# Voltage_Controlled_Amplifier_v1.net
KiCad netlist of a schematic drawn in EAGLE
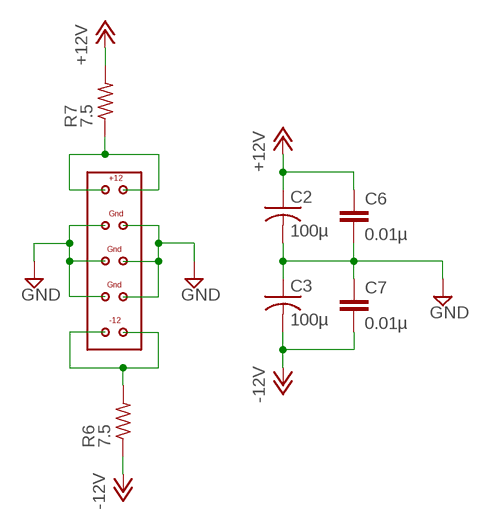
[diagram p0: schematic, sheet 1]
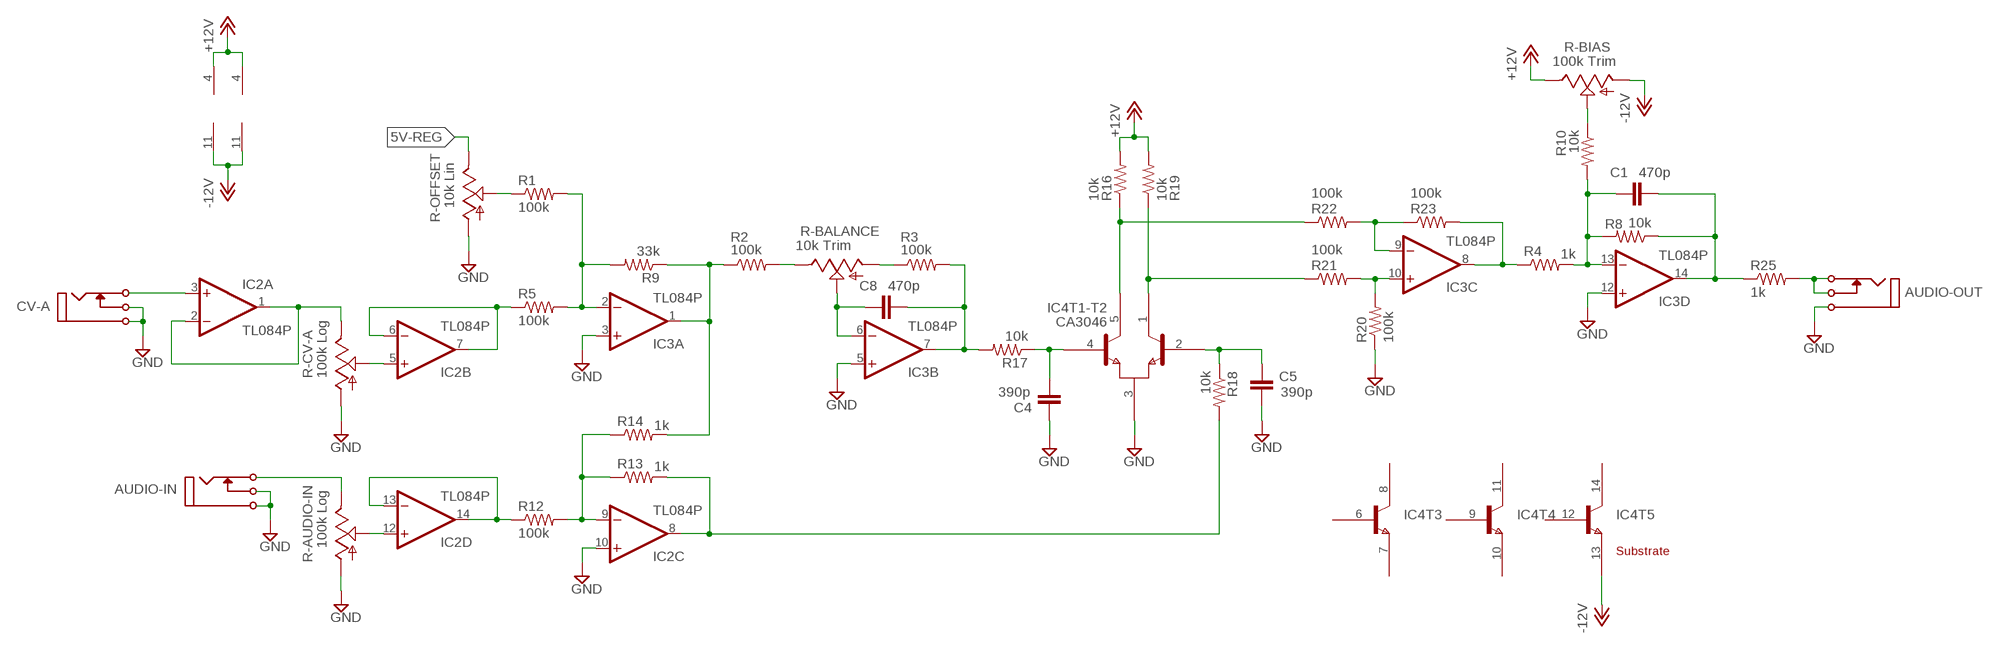
[diagram p1: schematic, sheet 2]

(export (version "E")
  (design (tool "Eeschema 10.0.6"))
  (components
    (comp (ref "C2")
      (value "100µ")
      (footprint "eagle-import:C025-050X050")
      (libsource (lib "eagle-import") (part "C-US025-050X050"))
    )
    (comp (ref "C3")
      (value "100µ")
      (footprint "eagle-import:C025-050X050")
      (libsource (lib "eagle-import") (part "C-US025-050X050"))
    )
    (comp (ref "C6")
      (value "0.01µ")
      (footprint "eagle-import:C2.5-2")
      (libsource (lib "eagle-import") (part "C2.5/2"))
    )
    (comp (ref "C7")
      (value "0.01µ")
      (footprint "eagle-import:C2.5-2")
      (libsource (lib "eagle-import") (part "C2.5/2"))
    )
    (comp (ref "R6")
      (value "7.5")
      (footprint "eagle-import:0204_7")
      (libsource (lib "eagle-import") (part "R-US_0204/7"))
    )
    (comp (ref "R7")
      (value "7.5")
      (footprint "eagle-import:0204_7")
      (libsource (lib "eagle-import") (part "R-US_0204/7"))
    )
    (comp (ref "U$1")
      (value "EURORACK-POWER")
      (footprint "eagle-import:EURORACK-POWER")
      (libsource (lib "eagle-import") (part "EURORACK-POWER"))
    )
    (comp (ref "AUDIO-IN")
      (value "I/O")
      (footprint "eagle-import:MONO_JACK")
      (libsource (lib "eagle-import") (part "MONO_JACK"))
    )
    (comp (ref "AUDIO-OUT")
      (value "I/O")
      (footprint "eagle-import:MONO_JACK")
      (libsource (lib "eagle-import") (part "MONO_JACK"))
    )
    (comp (ref "C1")
      (value "470p")
      (footprint "eagle-import:C2.5-2")
      (libsource (lib "eagle-import") (part "C2.5/2"))
    )
    (comp (ref "C4")
      (value "390p")
      (footprint "eagle-import:C2.5-2")
      (libsource (lib "eagle-import") (part "C2.5/2"))
    )
    (comp (ref "C5")
      (value "390p")
      (footprint "eagle-import:C2.5-2")
      (libsource (lib "eagle-import") (part "C2.5/2"))
    )
    (comp (ref "C8")
      (value "470p")
      (footprint "eagle-import:C2.5-2")
      (libsource (lib "eagle-import") (part "C2.5/2"))
    )
    (comp (ref "CV-A")
      (value "I/O")
      (footprint "eagle-import:MONO_JACK")
      (libsource (lib "eagle-import") (part "MONO_JACK"))
    )
    (comp (ref "IC2")
      (value "TL084P")
      (footprint "eagle-import:DIL14")
      (libsource (lib "eagle-import") (part "TL084P"))
    )
    (comp (ref "IC3")
      (value "TL084P")
      (footprint "eagle-import:DIL14")
      (libsource (lib "eagle-import") (part "TL084P"))
    )
    (comp (ref "IC4")
      (value "CA3046")
      (footprint "eagle-import:DIL14")
      (libsource (lib "eagle-import") (part "CA3046"))
    )
    (comp (ref "R-AUDIO-IN")
      (value "100k Log")
      (footprint "eagle-import:B64Y")
      (libsource (lib "eagle-import") (part "TRIM_US-B64Y"))
    )
    (comp (ref "R-BALANCE")
      (value "10k Trim")
      (footprint "eagle-import:B64Y")
      (libsource (lib "eagle-import") (part "TRIM_US-B64Y"))
    )
    (comp (ref "R-BIAS")
      (value "100k Trim")
      (footprint "eagle-import:B64Y")
      (libsource (lib "eagle-import") (part "TRIM_US-B64Y"))
    )
    (comp (ref "R-CV-A")
      (value "100k Log")
      (footprint "eagle-import:B64Y")
      (libsource (lib "eagle-import") (part "TRIM_US-B64Y"))
    )
    (comp (ref "R-OFFSET")
      (value "10k Lin")
      (footprint "eagle-import:B64Y")
      (libsource (lib "eagle-import") (part "TRIM_US-B64Y"))
    )
    (comp (ref "R1")
      (value "100k")
      (footprint "eagle-import:0204V")
      (libsource (lib "eagle-import") (part "R-US_0204/2V"))
    )
    (comp (ref "R2")
      (value "100k")
      (footprint "eagle-import:0204V")
      (libsource (lib "eagle-import") (part "R-US_0204/2V"))
    )
    (comp (ref "R3")
      (value "100k")
      (footprint "eagle-import:0204V")
      (libsource (lib "eagle-import") (part "R-US_0204/2V"))
    )
    (comp (ref "R4")
      (value "1k")
      (footprint "eagle-import:0204V")
      (libsource (lib "eagle-import") (part "R-US_0204/2V"))
    )
    (comp (ref "R5")
      (value "100k")
      (footprint "eagle-import:0204V")
      (libsource (lib "eagle-import") (part "R-US_0204/2V"))
    )
    (comp (ref "R8")
      (value "10k")
      (footprint "eagle-import:0204V")
      (libsource (lib "eagle-import") (part "R-US_0204/2V"))
    )
    (comp (ref "R9")
      (value "33k")
      (footprint "eagle-import:0204V")
      (libsource (lib "eagle-import") (part "R-US_0204/2V"))
    )
    (comp (ref "R10")
      (value "10k")
      (footprint "eagle-import:0204V")
      (libsource (lib "eagle-import") (part "R-US_0204/2V"))
    )
    (comp (ref "R12")
      (value "100k")
      (footprint "eagle-import:0204V")
      (libsource (lib "eagle-import") (part "R-US_0204/2V"))
    )
    (comp (ref "R13")
      (value "1k")
      (footprint "eagle-import:0204V")
      (libsource (lib "eagle-import") (part "R-US_0204/2V"))
    )
    (comp (ref "R14")
      (value "1k")
      (footprint "eagle-import:0204V")
      (libsource (lib "eagle-import") (part "R-US_0204/2V"))
    )
    (comp (ref "R16")
      (value "10k")
      (footprint "eagle-import:0204V")
      (libsource (lib "eagle-import") (part "R-US_0204/2V"))
    )
    (comp (ref "R17")
      (value "10k")
      (footprint "eagle-import:0204V")
      (libsource (lib "eagle-import") (part "R-US_0204/2V"))
    )
    (comp (ref "R18")
      (value "10k")
      (footprint "eagle-import:0204_7")
      (libsource (lib "eagle-import") (part "R-US_0204/7"))
    )
    (comp (ref "R19")
      (value "10k")
      (footprint "eagle-import:0204V")
      (libsource (lib "eagle-import") (part "R-US_0204/2V"))
    )
    (comp (ref "R20")
      (value "100k")
      (footprint "eagle-import:0204V")
      (libsource (lib "eagle-import") (part "R-US_0204/2V"))
    )
    (comp (ref "R21")
      (value "100k")
      (footprint "eagle-import:0204V")
      (libsource (lib "eagle-import") (part "R-US_0204/2V"))
    )
    (comp (ref "R22")
      (value "100k")
      (footprint "eagle-import:0204V")
      (libsource (lib "eagle-import") (part "R-US_0204/2V"))
    )
    (comp (ref "R23")
      (value "100k")
      (footprint "eagle-import:0204V")
      (libsource (lib "eagle-import") (part "R-US_0204/2V"))
    )
    (comp (ref "R25")
      (value "1k")
      (footprint "eagle-import:0204_7")
      (libsource (lib "eagle-import") (part "R-US_0204/7"))
    )
  )
  (nets
    (net (code "1") (name "+12V") (class "Default")
      (node (ref "C2") (pin "1") (pinfunction "1_1") (pintype "passive"))
      (node (ref "C6") (pin "1") (pinfunction "1_1") (pintype "passive"))
      (node (ref "IC2") (pin "4") (pinfunction "V+_4") (pintype "power_in"))
      (node (ref "IC3") (pin "4") (pinfunction "V+_4") (pintype "power_in"))
      (node (ref "R-BIAS") (pin "E") (pinfunction "E_E") (pintype "passive"))
      (node (ref "R16") (pin "2") (pinfunction "2_2") (pintype "passive"))
      (node (ref "R19") (pin "2") (pinfunction "2_2") (pintype "passive"))
      (node (ref "R7") (pin "2") (pinfunction "2_2") (pintype "passive"))
    )
    (net (code "2") (name "-12V") (class "Default")
      (node (ref "C3") (pin "2") (pinfunction "2_2") (pintype "passive"))
      (node (ref "C7") (pin "2") (pinfunction "2_2") (pintype "passive"))
      (node (ref "IC2") (pin "11") (pinfunction "V-_11") (pintype "power_in"))
      (node (ref "IC3") (pin "11") (pinfunction "V-_11") (pintype "power_in"))
      (node (ref "IC4") (pin "13") (pinfunction "E_13") (pintype "passive"))
      (node (ref "R-BIAS") (pin "A") (pinfunction "A_A") (pintype "passive"))
      (node (ref "R6") (pin "1") (pinfunction "1_1") (pintype "passive"))
    )
    (net (code "3") (name "5V-REG") (class "Default")
      (node (ref "R-OFFSET") (pin "E") (pinfunction "E_E") (pintype "passive"))
    )
    (net (code "4") (name "GND") (class "Default")
      (node (ref "AUDIO-IN") (pin "P$1") (pinfunction "P$1_P$1") (pintype "bidirectional"))
      (node (ref "AUDIO-IN") (pin "P$3") (pinfunction "P3_P$3") (pintype "bidirectional"))
      (node (ref "AUDIO-OUT") (pin "P$1") (pinfunction "P$1_P$1") (pintype "bidirectional"))
      (node (ref "C2") (pin "2") (pinfunction "2_2") (pintype "passive"))
      (node (ref "C3") (pin "1") (pinfunction "1_1") (pintype "passive"))
      (node (ref "C4") (pin "1") (pinfunction "1_1") (pintype "passive"))
      (node (ref "C5") (pin "2") (pinfunction "2_2") (pintype "passive"))
      (node (ref "C6") (pin "2") (pinfunction "2_2") (pintype "passive"))
      (node (ref "C7") (pin "1") (pinfunction "1_1") (pintype "passive"))
      (node (ref "CV-A") (pin "P$1") (pinfunction "P$1_P$1") (pintype "bidirectional"))
      (node (ref "CV-A") (pin "P$3") (pinfunction "P3_P$3") (pintype "bidirectional"))
      (node (ref "IC2") (pin "10") (pinfunction "+IN_10") (pintype "input"))
      (node (ref "IC3") (pin "12") (pinfunction "+IN_12") (pintype "input"))
      (node (ref "IC3") (pin "3") (pinfunction "+IN_3") (pintype "input"))
      (node (ref "IC3") (pin "5") (pinfunction "+IN_5") (pintype "input"))
      (node (ref "IC4") (pin "3") (pinfunction "E_3") (pintype "passive"))
      (node (ref "R-AUDIO-IN") (pin "A") (pinfunction "A_A") (pintype "passive"))
      (node (ref "R-CV-A") (pin "A") (pinfunction "A_A") (pintype "passive"))
      (node (ref "R-OFFSET") (pin "A") (pinfunction "A_A") (pintype "passive"))
      (node (ref "R20") (pin "1") (pinfunction "1_1") (pintype "passive"))
      (node (ref "U$1") (pin "P$3") (pinfunction "P$3_P$3") (pintype "bidirectional"))
      (node (ref "U$1") (pin "P$4") (pinfunction "P$4_P$4") (pintype "bidirectional"))
      (node (ref "U$1") (pin "P$5") (pinfunction "P$5_P$5") (pintype "bidirectional"))
      (node (ref "U$1") (pin "P$6") (pinfunction "P$6_P$6") (pintype "bidirectional"))
      (node (ref "U$1") (pin "P$7") (pinfunction "P$7_P$7") (pintype "bidirectional"))
      (node (ref "U$1") (pin "P$8") (pinfunction "P$8_P$8") (pintype "bidirectional"))
    )
    (net (code "5") (name "Net-(AUDIO-IN-P2)") (class "Default")
      (node (ref "AUDIO-IN") (pin "P$2") (pinfunction "P2_P$2") (pintype "bidirectional"))
      (node (ref "R-AUDIO-IN") (pin "E") (pinfunction "E_E") (pintype "passive"))
    )
    (net (code "6") (name "Net-(AUDIO-OUT-P2)") (class "Default")
      (node (ref "AUDIO-OUT") (pin "P$2") (pinfunction "P2_P$2") (pintype "bidirectional"))
      (node (ref "AUDIO-OUT") (pin "P$3") (pinfunction "P3_P$3") (pintype "bidirectional"))
      (node (ref "R25") (pin "2") (pinfunction "2_2") (pintype "passive"))
    )
    (net (code "7") (name "Net-(CV-A-P2)") (class "Default")
      (node (ref "CV-A") (pin "P$2") (pinfunction "P2_P$2") (pintype "bidirectional"))
      (node (ref "IC2") (pin "3") (pinfunction "+IN_3") (pintype "input"))
    )
    (net (code "8") (name "Net-(IC2A--IN)") (class "Default")
      (node (ref "IC2") (pin "1") (pinfunction "OUT_1") (pintype "output"))
      (node (ref "IC2") (pin "2") (pinfunction "-IN_2") (pintype "input"))
      (node (ref "R-CV-A") (pin "E") (pinfunction "E_E") (pintype "passive"))
    )
    (net (code "9") (name "Net-(IC2B-+IN)") (class "Default")
      (node (ref "IC2") (pin "5") (pinfunction "+IN_5") (pintype "input"))
      (node (ref "R-CV-A") (pin "S") (pinfunction "S_S") (pintype "passive"))
    )
    (net (code "10") (name "Net-(IC2B--IN)") (class "Default")
      (node (ref "IC2") (pin "6") (pinfunction "-IN_6") (pintype "input"))
      (node (ref "IC2") (pin "7") (pinfunction "OUT_7") (pintype "output"))
      (node (ref "R5") (pin "1") (pinfunction "1_1") (pintype "passive"))
    )
    (net (code "11") (name "Net-(IC2C--IN)") (class "Default")
      (node (ref "IC2") (pin "9") (pinfunction "-IN_9") (pintype "input"))
      (node (ref "R12") (pin "2") (pinfunction "2_2") (pintype "passive"))
      (node (ref "R13") (pin "1") (pinfunction "1_1") (pintype "passive"))
      (node (ref "R14") (pin "1") (pinfunction "1_1") (pintype "passive"))
    )
    (net (code "12") (name "Net-(IC2C-OUT)") (class "Default")
      (node (ref "IC2") (pin "8") (pinfunction "OUT_8") (pintype "output"))
      (node (ref "R13") (pin "2") (pinfunction "2_2") (pintype "passive"))
      (node (ref "R18") (pin "2") (pinfunction "2_2") (pintype "passive"))
    )
    (net (code "13") (name "Net-(IC2D-+IN)") (class "Default")
      (node (ref "IC2") (pin "12") (pinfunction "+IN_12") (pintype "input"))
      (node (ref "R-AUDIO-IN") (pin "S") (pinfunction "S_S") (pintype "passive"))
    )
    (net (code "14") (name "Net-(IC2D--IN)") (class "Default")
      (node (ref "IC2") (pin "13") (pinfunction "-IN_13") (pintype "input"))
      (node (ref "IC2") (pin "14") (pinfunction "OUT_14") (pintype "output"))
      (node (ref "R12") (pin "1") (pinfunction "1_1") (pintype "passive"))
    )
    (net (code "15") (name "Net-(IC3A--IN)") (class "Default")
      (node (ref "IC3") (pin "2") (pinfunction "-IN_2") (pintype "input"))
      (node (ref "R1") (pin "2") (pinfunction "2_2") (pintype "passive"))
      (node (ref "R5") (pin "2") (pinfunction "2_2") (pintype "passive"))
      (node (ref "R9") (pin "2") (pinfunction "2_2") (pintype "passive"))
    )
    (net (code "16") (name "Net-(IC3A-OUT)") (class "Default")
      (node (ref "IC3") (pin "1") (pinfunction "OUT_1") (pintype "output"))
      (node (ref "R14") (pin "2") (pinfunction "2_2") (pintype "passive"))
      (node (ref "R2") (pin "1") (pinfunction "1_1") (pintype "passive"))
      (node (ref "R9") (pin "1") (pinfunction "1_1") (pintype "passive"))
    )
    (net (code "17") (name "Net-(IC3B--IN)") (class "Default")
      (node (ref "C8") (pin "1") (pinfunction "1_1") (pintype "passive"))
      (node (ref "IC3") (pin "6") (pinfunction "-IN_6") (pintype "input"))
      (node (ref "R-BALANCE") (pin "S") (pinfunction "S_S") (pintype "passive"))
    )
    (net (code "18") (name "Net-(IC3B-OUT)") (class "Default")
      (node (ref "C8") (pin "2") (pinfunction "2_2") (pintype "passive"))
      (node (ref "IC3") (pin "7") (pinfunction "OUT_7") (pintype "output"))
      (node (ref "R17") (pin "2") (pinfunction "2_2") (pintype "passive"))
      (node (ref "R3") (pin "2") (pinfunction "2_2") (pintype "passive"))
    )
    (net (code "19") (name "Net-(IC3C-+IN)") (class "Default")
      (node (ref "IC3") (pin "10") (pinfunction "+IN_10") (pintype "input"))
      (node (ref "R20") (pin "2") (pinfunction "2_2") (pintype "passive"))
      (node (ref "R21") (pin "2") (pinfunction "2_2") (pintype "passive"))
    )
    (net (code "20") (name "Net-(IC3C--IN)") (class "Default")
      (node (ref "IC3") (pin "9") (pinfunction "-IN_9") (pintype "input"))
      (node (ref "R22") (pin "2") (pinfunction "2_2") (pintype "passive"))
      (node (ref "R23") (pin "1") (pinfunction "1_1") (pintype "passive"))
    )
    (net (code "21") (name "Net-(IC3C-OUT)") (class "Default")
      (node (ref "IC3") (pin "8") (pinfunction "OUT_8") (pintype "output"))
      (node (ref "R23") (pin "2") (pinfunction "2_2") (pintype "passive"))
      (node (ref "R4") (pin "1") (pinfunction "1_1") (pintype "passive"))
    )
    (net (code "22") (name "Net-(IC3D--IN)") (class "Default")
      (node (ref "C1") (pin "1") (pinfunction "1_1") (pintype "passive"))
      (node (ref "IC3") (pin "13") (pinfunction "-IN_13") (pintype "input"))
      (node (ref "R10") (pin "2") (pinfunction "2_2") (pintype "passive"))
      (node (ref "R4") (pin "2") (pinfunction "2_2") (pintype "passive"))
      (node (ref "R8") (pin "2") (pinfunction "2_2") (pintype "passive"))
    )
    (net (code "23") (name "Net-(IC3D-OUT)") (class "Default")
      (node (ref "C1") (pin "2") (pinfunction "2_2") (pintype "passive"))
      (node (ref "IC3") (pin "14") (pinfunction "OUT_14") (pintype "output"))
      (node (ref "R25") (pin "1") (pinfunction "1_1") (pintype "passive"))
      (node (ref "R8") (pin "1") (pinfunction "1_1") (pintype "passive"))
    )
    (net (code "24") (name "Net-(IC4A-B1)") (class "Default")
      (node (ref "C5") (pin "1") (pinfunction "1_1") (pintype "passive"))
      (node (ref "IC4") (pin "2") (pinfunction "B1_2") (pintype "passive"))
      (node (ref "R18") (pin "1") (pinfunction "1_1") (pintype "passive"))
    )
    (net (code "25") (name "Net-(IC4A-B2)") (class "Default")
      (node (ref "C4") (pin "2") (pinfunction "2_2") (pintype "passive"))
      (node (ref "IC4") (pin "4") (pinfunction "B2_4") (pintype "passive"))
      (node (ref "R17") (pin "1") (pinfunction "1_1") (pintype "passive"))
    )
    (net (code "26") (name "Net-(IC4A-C1)") (class "Default")
      (node (ref "IC4") (pin "1") (pinfunction "C1_1") (pintype "passive"))
      (node (ref "R19") (pin "1") (pinfunction "1_1") (pintype "passive"))
      (node (ref "R21") (pin "1") (pinfunction "1_1") (pintype "passive"))
    )
    (net (code "27") (name "Net-(IC4A-C2)") (class "Default")
      (node (ref "IC4") (pin "5") (pinfunction "C2_5") (pintype "passive"))
      (node (ref "R16") (pin "1") (pinfunction "1_1") (pintype "passive"))
      (node (ref "R22") (pin "1") (pinfunction "1_1") (pintype "passive"))
    )
    (net (code "28") (name "Net-(R-BALANCE-PadA)") (class "Default")
      (node (ref "R-BALANCE") (pin "A") (pinfunction "A_A") (pintype "passive"))
      (node (ref "R3") (pin "1") (pinfunction "1_1") (pintype "passive"))
    )
    (net (code "29") (name "Net-(R-BALANCE-PadE)") (class "Default")
      (node (ref "R-BALANCE") (pin "E") (pinfunction "E_E") (pintype "passive"))
      (node (ref "R2") (pin "2") (pinfunction "2_2") (pintype "passive"))
    )
    (net (code "30") (name "Net-(R-BIAS-PadS)") (class "Default")
      (node (ref "R-BIAS") (pin "S") (pinfunction "S_S") (pintype "passive"))
      (node (ref "R10") (pin "1") (pinfunction "1_1") (pintype "passive"))
    )
    (net (code "31") (name "Net-(R-OFFSET-PadS)") (class "Default")
      (node (ref "R-OFFSET") (pin "S") (pinfunction "S_S") (pintype "passive"))
      (node (ref "R1") (pin "1") (pinfunction "1_1") (pintype "passive"))
    )
    (net (code "32") (name "Net-(R6-Pad2)") (class "Default")
      (node (ref "R6") (pin "2") (pinfunction "2_2") (pintype "passive"))
      (node (ref "U$1") (pin "P$10") (pinfunction "P$10_P$10") (pintype "bidirectional"))
      (node (ref "U$1") (pin "P$9") (pinfunction "P$9_P$9") (pintype "bidirectional"))
    )
    (net (code "33") (name "Net-(R7-Pad1)") (class "Default")
      (node (ref "R7") (pin "1") (pinfunction "1_1") (pintype "passive"))
      (node (ref "U$1") (pin "P$1") (pinfunction "P$1_P$1") (pintype "bidirectional"))
      (node (ref "U$1") (pin "P$2") (pinfunction "P$2_P$2") (pintype "bidirectional"))
    )
    (net (code "34") (name "unconnected-(IC4B-B-Pad6)") (class "Default")
      (node (ref "IC4") (pin "6") (pinfunction "B_6") (pintype "passive"))
    )
    (net (code "35") (name "unconnected-(IC4B-C-Pad8)") (class "Default")
      (node (ref "IC4") (pin "8") (pinfunction "C_8") (pintype "passive"))
    )
    (net (code "36") (name "unconnected-(IC4B-E-Pad7)") (class "Default")
      (node (ref "IC4") (pin "7") (pinfunction "E_7") (pintype "passive"))
    )
    (net (code "37") (name "unconnected-(IC4C-B-Pad9)") (class "Default")
      (node (ref "IC4") (pin "9") (pinfunction "B_9") (pintype "passive"))
    )
    (net (code "38") (name "unconnected-(IC4C-C-Pad11)") (class "Default")
      (node (ref "IC4") (pin "11") (pinfunction "C_11") (pintype "passive"))
    )
    (net (code "39") (name "unconnected-(IC4C-E-Pad10)") (class "Default")
      (node (ref "IC4") (pin "10") (pinfunction "E_10") (pintype "passive"))
    )
    (net (code "40") (name "unconnected-(IC4D-B-Pad12)") (class "Default")
      (node (ref "IC4") (pin "12") (pinfunction "B_12") (pintype "passive"))
    )
    (net (code "41") (name "unconnected-(IC4D-C-Pad14)") (class "Default")
      (node (ref "IC4") (pin "14") (pinfunction "C_14") (pintype "passive"))
    )
  )
)
